# interface1.net
KiCad netlist of a schematic drawn in Altium Designer
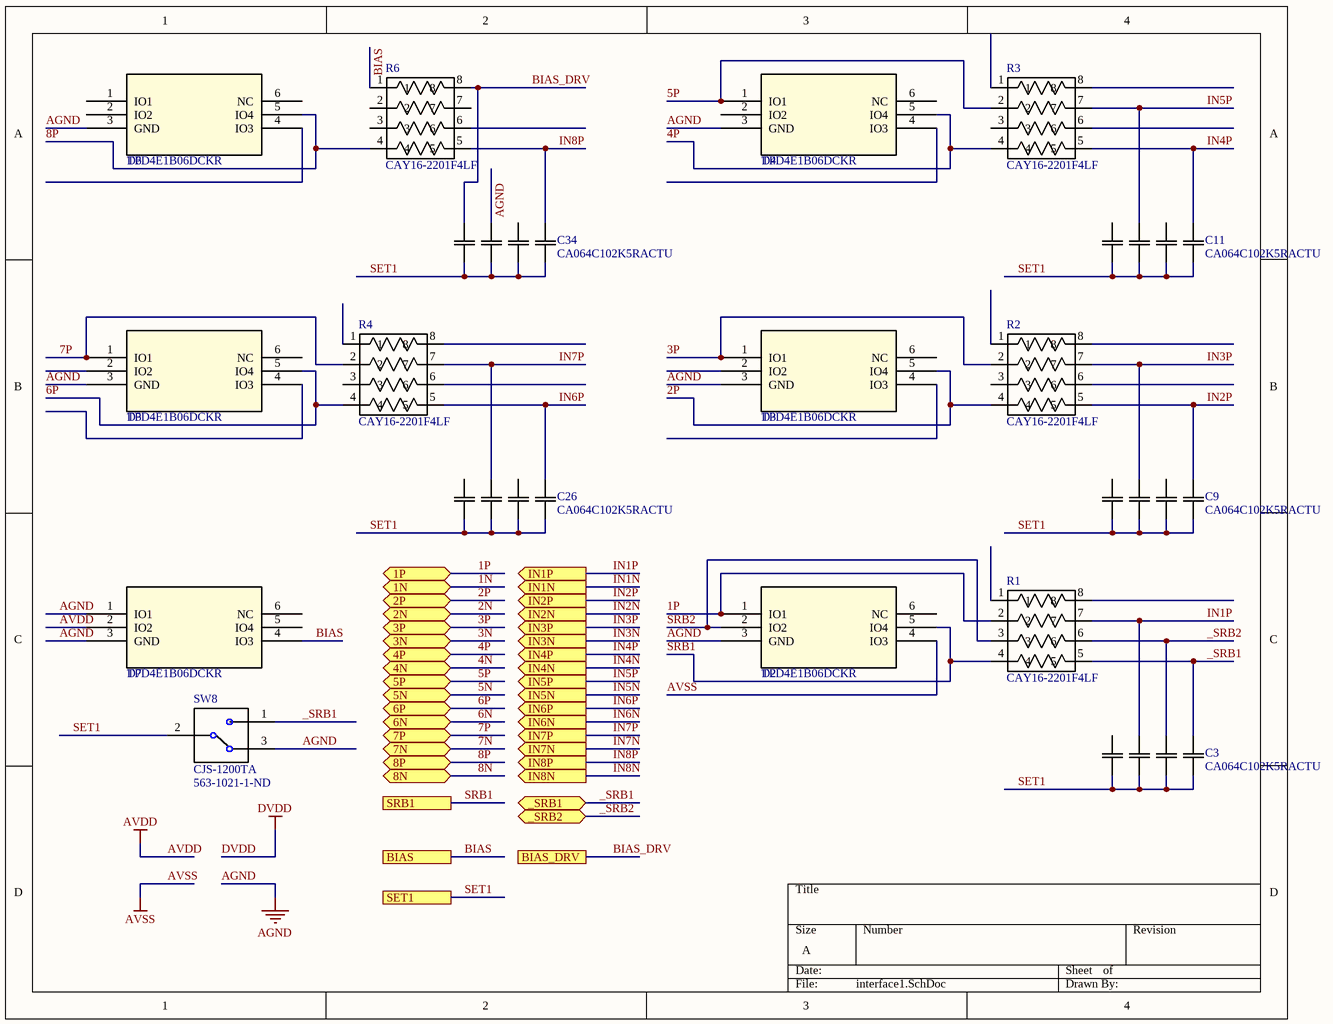
[diagram p0: interface1.SchDoc]

(export (version "E")
  (design (tool "Eeschema 10.0.6"))
  (components
    (comp (ref "C3")
      (value "CA064C102K5RACTU")
      (footprint "CA064")
      (description "CAP ARRAY 1000PF 50V X7R 0612")
      (fields (field (name "TOLERANCE") "10%"))
      (libsource (lib "EE_smallOB_BW_v1.0") (part "CA064C102K5RACTU"))
    )
    (comp (ref "C9")
      (value "CA064C102K5RACTU")
      (footprint "CA064")
      (description "CAP ARRAY 1000PF 50V X7R 0612")
      (fields (field (name "TOLERANCE") "10%"))
      (libsource (lib "EE_smallOB_BW_v1.0") (part "CA064C102K5RACTU"))
    )
    (comp (ref "C11")
      (value "CA064C102K5RACTU")
      (footprint "CA064")
      (description "CAP ARRAY 1000PF 50V X7R 0612")
      (fields (field (name "TOLERANCE") "10%"))
      (libsource (lib "EE_smallOB_BW_v1.0") (part "CA064C102K5RACTU"))
    )
    (comp (ref "C26")
      (value "CA064C102K5RACTU")
      (footprint "CA064")
      (description "CAP ARRAY 1000PF 50V X7R 0612")
      (fields (field (name "TOLERANCE") "10%"))
      (libsource (lib "EE_smallOB_BW_v1.0") (part "CA064C102K5RACTU"))
    )
    (comp (ref "C34")
      (value "CA064C102K5RACTU")
      (footprint "CA064")
      (description "CAP ARRAY 1000PF 50V X7R 0612")
      (fields (field (name "TOLERANCE") "10%"))
      (libsource (lib "EE_smallOB_BW_v1.0") (part "CA064C102K5RACTU"))
    )
    (comp (ref "D2")
      (value "TPD4E1B06DCKR")
      (footprint "DCK6")
      (description "TVS DIODE 5.5VWM 14.5VC SC70-6")
      (libsource (lib "EE_smallOB_BW_v1.0") (part "TPD4E1B06DCKR"))
    )
    (comp (ref "D3")
      (value "TPD4E1B06DCKR")
      (footprint "DCK6")
      (description "TVS DIODE 5.5VWM 14.5VC SC70-6")
      (libsource (lib "EE_smallOB_BW_v1.0") (part "TPD4E1B06DCKR"))
    )
    (comp (ref "D4")
      (value "TPD4E1B06DCKR")
      (footprint "DCK6")
      (description "TVS DIODE 5.5VWM 14.5VC SC70-6")
      (libsource (lib "EE_smallOB_BW_v1.0") (part "TPD4E1B06DCKR"))
    )
    (comp (ref "D5")
      (value "TPD4E1B06DCKR")
      (footprint "DCK6")
      (description "TVS DIODE 5.5VWM 14.5VC SC70-6")
      (libsource (lib "EE_smallOB_BW_v1.0") (part "TPD4E1B06DCKR"))
    )
    (comp (ref "D6")
      (value "TPD4E1B06DCKR")
      (footprint "DCK6")
      (description "TVS DIODE 5.5VWM 14.5VC SC70-6")
      (libsource (lib "EE_smallOB_BW_v1.0") (part "TPD4E1B06DCKR"))
    )
    (comp (ref "D7")
      (value "TPD4E1B06DCKR")
      (footprint "DCK6")
      (description "TVS DIODE 5.5VWM 14.5VC SC70-6")
      (libsource (lib "EE_smallOB_BW_v1.0") (part "TPD4E1B06DCKR"))
    )
    (comp (ref "R1")
      (value "CAY16-2201F4LF")
      (footprint "*RESCAXE80P320X160-8N")
      (description "BOURNS         CAY16-2201F4LF             RESISTOR, ARRAY-4, 2.2KOHM, 5%, SMD")
      (fields (field (name "TOLERANCE") "1%"))
      (libsource (lib "EE_smallOB_BW_v1.0") (part "CAY16-2201F4LF"))
    )
    (comp (ref "R2")
      (value "CAY16-2201F4LF")
      (footprint "*RESCAXE80P320X160-8N")
      (description "BOURNS         CAY16-2201F4LF             RESISTOR, ARRAY-4, 2.2KOHM, 5%, SMD")
      (fields (field (name "TOLERANCE") "1%"))
      (libsource (lib "EE_smallOB_BW_v1.0") (part "CAY16-2201F4LF"))
    )
    (comp (ref "R3")
      (value "CAY16-2201F4LF")
      (footprint "*RESCAXE80P320X160-8N")
      (description "BOURNS         CAY16-2201F4LF             RESISTOR, ARRAY-4, 2.2KOHM, 5%, SMD")
      (fields (field (name "TOLERANCE") "1%"))
      (libsource (lib "EE_smallOB_BW_v1.0") (part "CAY16-2201F4LF"))
    )
    (comp (ref "R4")
      (value "CAY16-2201F4LF")
      (footprint "*RESCAXE80P320X160-8N")
      (description "BOURNS         CAY16-2201F4LF             RESISTOR, ARRAY-4, 2.2KOHM, 5%, SMD")
      (fields (field (name "TOLERANCE") "1%"))
      (libsource (lib "EE_smallOB_BW_v1.0") (part "CAY16-2201F4LF"))
    )
    (comp (ref "R6")
      (value "CAY16-2201F4LF")
      (footprint "*RESCAXE80P320X160-8N")
      (description "BOURNS         CAY16-2201F4LF             RESISTOR, ARRAY-4, 2.2KOHM, 5%, SMD")
      (fields (field (name "TOLERANCE") "1%"))
      (libsource (lib "EE_smallOB_BW_v1.0") (part "CAY16-2201F4LF"))
    )
    (comp (ref "SW8")
      (value "CJS-1200TA")
      (footprint "*SW_CJS-1200TA")
      (description "SWITCH SLIDE SPDT 100MA 6V")
      (fields (field (name "SUPPLIER PART NUMBER 1") "563-1021-1-ND"))
      (libsource (lib "EE_smallOB_BW_v1.0") (part "CJS-1200TA"))
    )
  )
  (nets
    (net (code "2") (name "/1P") (class "Default")
      (node (ref "D2") (pin "1") (pinfunction "IO1_1") (pintype "passive"))
      (node (ref "R1") (pin "2") (pinfunction "2_2") (pintype "passive"))
    )
    (net (code "4") (name "/2P") (class "Default")
      (node (ref "D3") (pin "5") (pinfunction "IO4_5") (pintype "passive"))
      (node (ref "R2") (pin "4") (pinfunction "4_4") (pintype "passive"))
    )
    (net (code "6") (name "/3P") (class "Default")
      (node (ref "D3") (pin "1") (pinfunction "IO1_1") (pintype "passive"))
      (node (ref "R2") (pin "2") (pinfunction "2_2") (pintype "passive"))
    )
    (net (code "8") (name "/4P") (class "Default")
      (node (ref "D4") (pin "5") (pinfunction "IO4_5") (pintype "passive"))
      (node (ref "R3") (pin "4") (pinfunction "4_4") (pintype "passive"))
    )
    (net (code "10") (name "/5P") (class "Default")
      (node (ref "D4") (pin "1") (pinfunction "IO1_1") (pintype "passive"))
      (node (ref "R3") (pin "2") (pinfunction "2_2") (pintype "passive"))
    )
    (net (code "12") (name "/6P") (class "Default")
      (node (ref "D5") (pin "5") (pinfunction "IO4_5") (pintype "passive"))
      (node (ref "R4") (pin "4") (pinfunction "4_4") (pintype "passive"))
    )
    (net (code "14") (name "/7P") (class "Default")
      (node (ref "D5") (pin "1") (pinfunction "IO1_1") (pintype "passive"))
      (node (ref "R4") (pin "2") (pinfunction "2_2") (pintype "passive"))
    )
    (net (code "16") (name "/8P") (class "Default")
      (node (ref "D6") (pin "5") (pinfunction "IO4_5") (pintype "passive"))
      (node (ref "R6") (pin "4") (pinfunction "4_4") (pintype "passive"))
    )
    (net (code "17") (name "/BIAS") (class "Default")
      (node (ref "D7") (pin "4") (pinfunction "IO3_4") (pintype "passive"))
      (node (ref "R6") (pin "1") (pinfunction "1_1") (pintype "passive"))
    )
    (net (code "18") (name "/BIAS_DRV") (class "Default")
      (node (ref "C34") (pin "8") (pinfunction "8_8") (pintype "passive"))
      (node (ref "R6") (pin "8") (pinfunction "8_8") (pintype "passive"))
    )
    (net (code "20") (name "/IN1P") (class "Default")
      (node (ref "C3") (pin "7") (pinfunction "7_7") (pintype "passive"))
      (node (ref "R1") (pin "7") (pinfunction "7_7") (pintype "passive"))
    )
    (net (code "22") (name "/IN2P") (class "Default")
      (node (ref "C9") (pin "5") (pinfunction "5_5") (pintype "passive"))
      (node (ref "R2") (pin "5") (pinfunction "5_5") (pintype "passive"))
    )
    (net (code "24") (name "/IN3P") (class "Default")
      (node (ref "C9") (pin "7") (pinfunction "7_7") (pintype "passive"))
      (node (ref "R2") (pin "7") (pinfunction "7_7") (pintype "passive"))
    )
    (net (code "26") (name "/IN4P") (class "Default")
      (node (ref "C11") (pin "5") (pinfunction "5_5") (pintype "passive"))
      (node (ref "R3") (pin "5") (pinfunction "5_5") (pintype "passive"))
    )
    (net (code "28") (name "/IN5P") (class "Default")
      (node (ref "C11") (pin "7") (pinfunction "7_7") (pintype "passive"))
      (node (ref "R3") (pin "7") (pinfunction "7_7") (pintype "passive"))
    )
    (net (code "30") (name "/IN6P") (class "Default")
      (node (ref "C26") (pin "5") (pinfunction "5_5") (pintype "passive"))
      (node (ref "R4") (pin "5") (pinfunction "5_5") (pintype "passive"))
    )
    (net (code "32") (name "/IN7P") (class "Default")
      (node (ref "C26") (pin "7") (pinfunction "7_7") (pintype "passive"))
      (node (ref "R4") (pin "7") (pinfunction "7_7") (pintype "passive"))
    )
    (net (code "34") (name "/IN8P") (class "Default")
      (node (ref "C34") (pin "5") (pinfunction "5_5") (pintype "passive"))
      (node (ref "R6") (pin "5") (pinfunction "5_5") (pintype "passive"))
    )
    (net (code "35") (name "/SET1") (class "Default")
      (node (ref "C11") (pin "1") (pinfunction "1_1") (pintype "passive"))
      (node (ref "C11") (pin "2") (pinfunction "2_2") (pintype "passive"))
      (node (ref "C11") (pin "3") (pinfunction "3_3") (pintype "passive"))
      (node (ref "C11") (pin "4") (pinfunction "4_4") (pintype "passive"))
      (node (ref "C26") (pin "1") (pinfunction "1_1") (pintype "passive"))
      (node (ref "C26") (pin "2") (pinfunction "2_2") (pintype "passive"))
      (node (ref "C26") (pin "3") (pinfunction "3_3") (pintype "passive"))
      (node (ref "C26") (pin "4") (pinfunction "4_4") (pintype "passive"))
      (node (ref "C3") (pin "1") (pinfunction "1_1") (pintype "passive"))
      (node (ref "C3") (pin "2") (pinfunction "2_2") (pintype "passive"))
      (node (ref "C3") (pin "3") (pinfunction "3_3") (pintype "passive"))
      (node (ref "C3") (pin "4") (pinfunction "4_4") (pintype "passive"))
      (node (ref "C34") (pin "1") (pinfunction "1_1") (pintype "passive"))
      (node (ref "C34") (pin "2") (pinfunction "2_2") (pintype "passive"))
      (node (ref "C34") (pin "3") (pinfunction "3_3") (pintype "passive"))
      (node (ref "C34") (pin "4") (pinfunction "4_4") (pintype "passive"))
      (node (ref "C9") (pin "1") (pinfunction "1_1") (pintype "passive"))
      (node (ref "C9") (pin "2") (pinfunction "2_2") (pintype "passive"))
      (node (ref "C9") (pin "3") (pinfunction "3_3") (pintype "passive"))
      (node (ref "C9") (pin "4") (pinfunction "4_4") (pintype "passive"))
      (node (ref "SW8") (pin "2") (pinfunction "2_2") (pintype "passive"))
    )
    (net (code "36") (name "/SRB1") (class "Default")
      (node (ref "D2") (pin "5") (pinfunction "IO4_5") (pintype "passive"))
      (node (ref "R1") (pin "4") (pinfunction "4_4") (pintype "passive"))
    )
    (net (code "37") (name "/SRB2") (class "Default")
      (node (ref "D2") (pin "2") (pinfunction "IO2_2") (pintype "passive"))
      (node (ref "R1") (pin "3") (pinfunction "3_3") (pintype "passive"))
    )
    (net (code "38") (name "/_SRB1") (class "Default")
      (node (ref "C3") (pin "5") (pinfunction "5_5") (pintype "passive"))
      (node (ref "R1") (pin "5") (pinfunction "5_5") (pintype "passive"))
      (node (ref "SW8") (pin "1") (pinfunction "1_1") (pintype "passive"))
    )
    (net (code "39") (name "/_SRB2") (class "Default")
      (node (ref "C3") (pin "6") (pinfunction "6_6") (pintype "passive"))
      (node (ref "R1") (pin "6") (pinfunction "6_6") (pintype "passive"))
    )
    (net (code "40") (name "AGND") (class "Default")
      (node (ref "C34") (pin "7") (pinfunction "7_7") (pintype "passive"))
      (node (ref "D2") (pin "3") (pinfunction "GND_3") (pintype "power_in"))
      (node (ref "D3") (pin "3") (pinfunction "GND_3") (pintype "power_in"))
      (node (ref "D4") (pin "3") (pinfunction "GND_3") (pintype "power_in"))
      (node (ref "D5") (pin "3") (pinfunction "GND_3") (pintype "power_in"))
      (node (ref "D6") (pin "3") (pinfunction "GND_3") (pintype "power_in"))
      (node (ref "D7") (pin "1") (pinfunction "IO1_1") (pintype "passive"))
      (node (ref "D7") (pin "3") (pinfunction "GND_3") (pintype "power_in"))
      (node (ref "SW8") (pin "3") (pinfunction "3_3") (pintype "passive"))
    )
    (net (code "41") (name "AVDD") (class "Default")
      (node (ref "D7") (pin "2") (pinfunction "IO2_2") (pintype "passive"))
    )
    (net (code "42") (name "AVSS") (class "Default")
      (node (ref "D2") (pin "4") (pinfunction "IO3_4") (pintype "passive"))
    )
    (net (code "44") (name "unconnected-(C3-Pad8)") (class "Default")
      (node (ref "C3") (pin "8") (pinfunction "8_8") (pintype "passive"))
    )
    (net (code "45") (name "unconnected-(C9-Pad6)") (class "Default")
      (node (ref "C9") (pin "6") (pinfunction "6_6") (pintype "passive"))
    )
    (net (code "46") (name "unconnected-(C9-Pad8)") (class "Default")
      (node (ref "C9") (pin "8") (pinfunction "8_8") (pintype "passive"))
    )
    (net (code "47") (name "unconnected-(C11-Pad6)") (class "Default")
      (node (ref "C11") (pin "6") (pinfunction "6_6") (pintype "passive"))
    )
    (net (code "48") (name "unconnected-(C11-Pad8)") (class "Default")
      (node (ref "C11") (pin "8") (pinfunction "8_8") (pintype "passive"))
    )
    (net (code "49") (name "unconnected-(C26-Pad6)") (class "Default")
      (node (ref "C26") (pin "6") (pinfunction "6_6") (pintype "passive"))
    )
    (net (code "50") (name "unconnected-(C26-Pad8)") (class "Default")
      (node (ref "C26") (pin "8") (pinfunction "8_8") (pintype "passive"))
    )
    (net (code "51") (name "unconnected-(C34-Pad6)") (class "Default")
      (node (ref "C34") (pin "6") (pinfunction "6_6") (pintype "passive"))
    )
    (net (code "52") (name "unconnected-(D2-NC-Pad6)") (class "Default")
      (node (ref "D2") (pin "6") (pinfunction "NC_6") (pintype "passive"))
    )
    (net (code "53") (name "unconnected-(D3-IO2-Pad2)") (class "Default")
      (node (ref "D3") (pin "2") (pinfunction "IO2_2") (pintype "passive"))
    )
    (net (code "54") (name "unconnected-(D3-IO3-Pad4)") (class "Default")
      (node (ref "D3") (pin "4") (pinfunction "IO3_4") (pintype "passive"))
    )
    (net (code "55") (name "unconnected-(D3-NC-Pad6)") (class "Default")
      (node (ref "D3") (pin "6") (pinfunction "NC_6") (pintype "passive"))
    )
    (net (code "56") (name "unconnected-(D4-IO2-Pad2)") (class "Default")
      (node (ref "D4") (pin "2") (pinfunction "IO2_2") (pintype "passive"))
    )
    (net (code "57") (name "unconnected-(D4-IO3-Pad4)") (class "Default")
      (node (ref "D4") (pin "4") (pinfunction "IO3_4") (pintype "passive"))
    )
    (net (code "58") (name "unconnected-(D4-NC-Pad6)") (class "Default")
      (node (ref "D4") (pin "6") (pinfunction "NC_6") (pintype "passive"))
    )
    (net (code "59") (name "unconnected-(D5-IO2-Pad2)") (class "Default")
      (node (ref "D5") (pin "2") (pinfunction "IO2_2") (pintype "passive"))
    )
    (net (code "60") (name "unconnected-(D5-IO3-Pad4)") (class "Default")
      (node (ref "D5") (pin "4") (pinfunction "IO3_4") (pintype "passive"))
    )
    (net (code "61") (name "unconnected-(D5-NC-Pad6)") (class "Default")
      (node (ref "D5") (pin "6") (pinfunction "NC_6") (pintype "passive"))
    )
    (net (code "62") (name "unconnected-(D6-IO1-Pad1)") (class "Default")
      (node (ref "D6") (pin "1") (pinfunction "IO1_1") (pintype "passive"))
    )
    (net (code "63") (name "unconnected-(D6-IO2-Pad2)") (class "Default")
      (node (ref "D6") (pin "2") (pinfunction "IO2_2") (pintype "passive"))
    )
    (net (code "64") (name "unconnected-(D6-IO3-Pad4)") (class "Default")
      (node (ref "D6") (pin "4") (pinfunction "IO3_4") (pintype "passive"))
    )
    (net (code "65") (name "unconnected-(D6-NC-Pad6)") (class "Default")
      (node (ref "D6") (pin "6") (pinfunction "NC_6") (pintype "passive"))
    )
    (net (code "66") (name "unconnected-(D7-IO4-Pad5)") (class "Default")
      (node (ref "D7") (pin "5") (pinfunction "IO4_5") (pintype "passive"))
    )
    (net (code "67") (name "unconnected-(D7-NC-Pad6)") (class "Default")
      (node (ref "D7") (pin "6") (pinfunction "NC_6") (pintype "passive"))
    )
    (net (code "68") (name "unconnected-(R1-Pad1)") (class "Default")
      (node (ref "R1") (pin "1") (pinfunction "1_1") (pintype "passive"))
    )
    (net (code "69") (name "unconnected-(R1-Pad8)") (class "Default")
      (node (ref "R1") (pin "8") (pinfunction "8_8") (pintype "passive"))
    )
    (net (code "70") (name "unconnected-(R2-Pad1)") (class "Default")
      (node (ref "R2") (pin "1") (pinfunction "1_1") (pintype "passive"))
    )
    (net (code "71") (name "unconnected-(R2-Pad3)") (class "Default")
      (node (ref "R2") (pin "3") (pinfunction "3_3") (pintype "passive"))
    )
    (net (code "72") (name "unconnected-(R2-Pad6)") (class "Default")
      (node (ref "R2") (pin "6") (pinfunction "6_6") (pintype "passive"))
    )
    (net (code "73") (name "unconnected-(R2-Pad8)") (class "Default")
      (node (ref "R2") (pin "8") (pinfunction "8_8") (pintype "passive"))
    )
    (net (code "74") (name "unconnected-(R3-Pad1)") (class "Default")
      (node (ref "R3") (pin "1") (pinfunction "1_1") (pintype "passive"))
    )
    (net (code "75") (name "unconnected-(R3-Pad3)") (class "Default")
      (node (ref "R3") (pin "3") (pinfunction "3_3") (pintype "passive"))
    )
    (net (code "76") (name "unconnected-(R3-Pad6)") (class "Default")
      (node (ref "R3") (pin "6") (pinfunction "6_6") (pintype "passive"))
    )
    (net (code "77") (name "unconnected-(R3-Pad8)") (class "Default")
      (node (ref "R3") (pin "8") (pinfunction "8_8") (pintype "passive"))
    )
    (net (code "78") (name "unconnected-(R4-Pad1)") (class "Default")
      (node (ref "R4") (pin "1") (pinfunction "1_1") (pintype "passive"))
    )
    (net (code "79") (name "unconnected-(R4-Pad3)") (class "Default")
      (node (ref "R4") (pin "3") (pinfunction "3_3") (pintype "passive"))
    )
    (net (code "80") (name "unconnected-(R4-Pad6)") (class "Default")
      (node (ref "R4") (pin "6") (pinfunction "6_6") (pintype "passive"))
    )
    (net (code "81") (name "unconnected-(R4-Pad8)") (class "Default")
      (node (ref "R4") (pin "8") (pinfunction "8_8") (pintype "passive"))
    )
    (net (code "82") (name "unconnected-(R6-Pad2)") (class "Default")
      (node (ref "R6") (pin "2") (pinfunction "2_2") (pintype "passive"))
    )
    (net (code "83") (name "unconnected-(R6-Pad3)") (class "Default")
      (node (ref "R6") (pin "3") (pinfunction "3_3") (pintype "passive"))
    )
    (net (code "84") (name "unconnected-(R6-Pad6)") (class "Default")
      (node (ref "R6") (pin "6") (pinfunction "6_6") (pintype "passive"))
    )
    (net (code "85") (name "unconnected-(R6-Pad7)") (class "Default")
      (node (ref "R6") (pin "7") (pinfunction "7_7") (pintype "passive"))
    )
  )
)
